# usb.net
KiCad netlist of a schematic drawn in Altium Designer
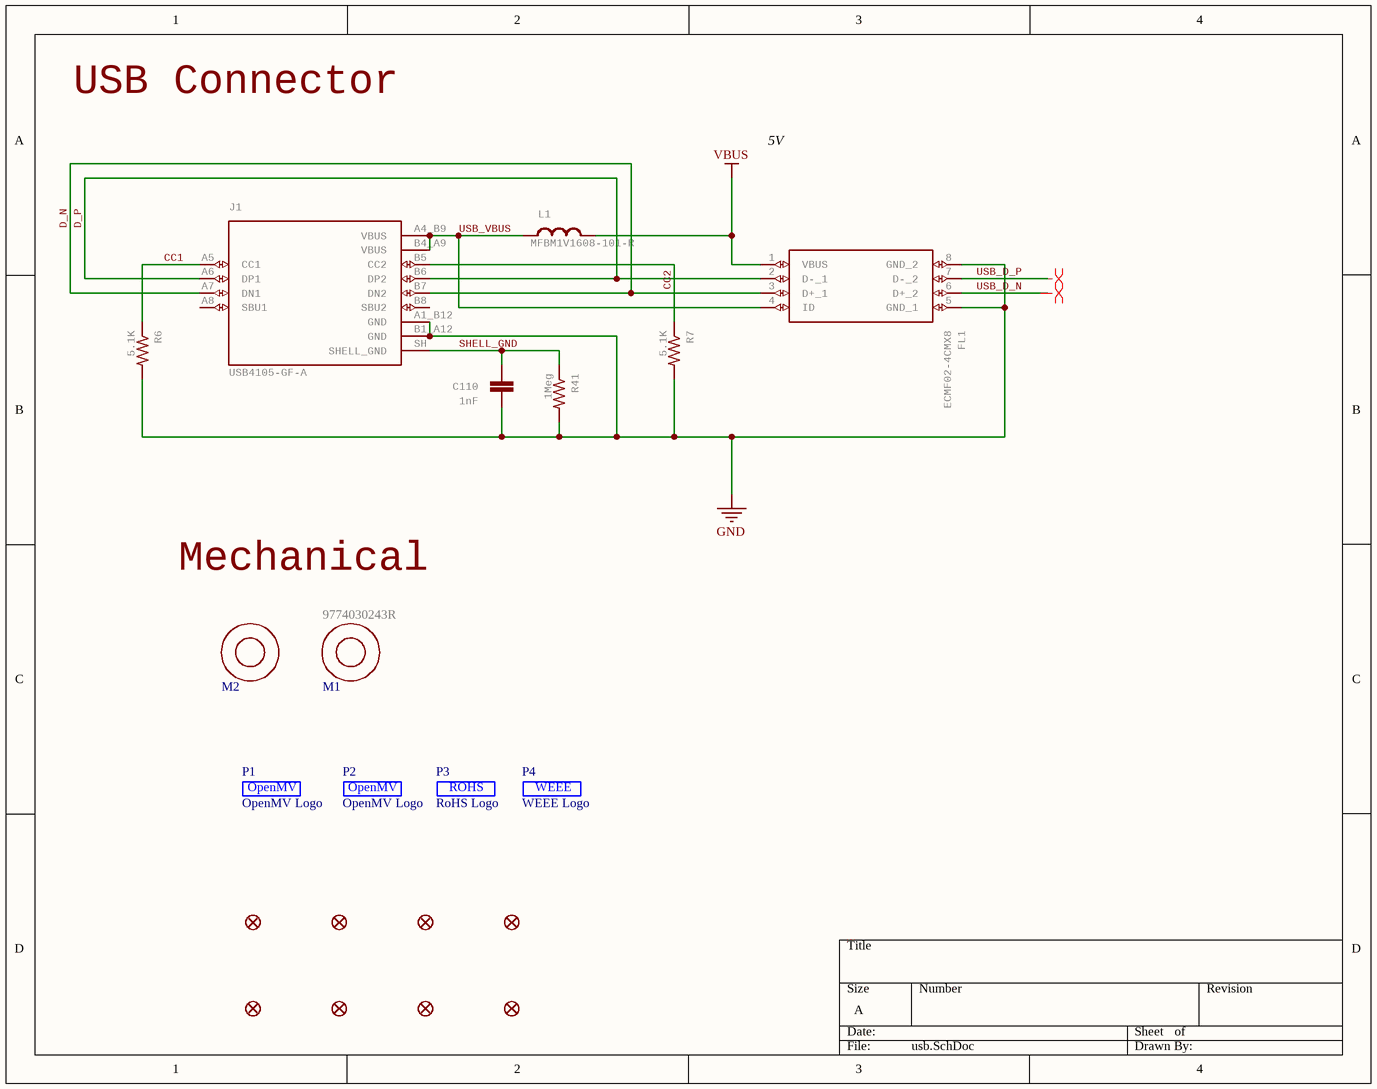
[diagram p0: usb.SchDoc]

(export (version "E")
  (design (tool "Eeschema 10.0.6"))
  (components
    (comp (ref "C110")
      (value "1nF")
      (footprint "0402-CAP")
      (description "Capacitor")
      (fields (field (name "MPN") "VJ0402Y102JXACW1BC"))
      (libsource (lib "rt10") (part "CAP0402-CAP"))
    )
    (comp (ref "FD1")
      (value "FIDUCIAL1X2")
      (footprint "FIDUCIAL-1X2")
      (fields (field (name "LIBRARYNAME") "SparkFun-Aesthetics"))
      (libsource (lib "rt10") (part "FIDUCIAL1X2"))
    )
    (comp (ref "FD2")
      (value "FIDUCIAL1X2")
      (footprint "FIDUCIAL-1X2")
      (fields (field (name "LIBRARYNAME") "SparkFun-Aesthetics"))
      (libsource (lib "rt10") (part "FIDUCIAL1X2"))
    )
    (comp (ref "FD3")
      (value "FIDUCIAL1X2")
      (footprint "FIDUCIAL-1X2")
      (fields (field (name "LIBRARYNAME") "SparkFun-Aesthetics"))
      (libsource (lib "rt10") (part "FIDUCIAL1X2"))
    )
    (comp (ref "FD4")
      (value "FIDUCIAL1X2")
      (footprint "FIDUCIAL-1X2")
      (fields (field (name "LIBRARYNAME") "SparkFun-Aesthetics"))
      (libsource (lib "rt10") (part "FIDUCIAL1X2"))
    )
    (comp (ref "FD5")
      (value "FIDUCIAL1X2")
      (footprint "FIDUCIAL-1X2")
      (fields (field (name "LIBRARYNAME") "SparkFun-Aesthetics"))
      (libsource (lib "rt10") (part "FIDUCIAL1X2"))
    )
    (comp (ref "FD6")
      (value "FIDUCIAL1X2")
      (footprint "FIDUCIAL-1X2")
      (fields (field (name "LIBRARYNAME") "SparkFun-Aesthetics"))
      (libsource (lib "rt10") (part "FIDUCIAL1X2"))
    )
    (comp (ref "FD7")
      (value "FIDUCIAL1X2")
      (footprint "FIDUCIAL-1X2")
      (fields (field (name "LIBRARYNAME") "SparkFun-Aesthetics"))
      (libsource (lib "rt10") (part "FIDUCIAL1X2"))
    )
    (comp (ref "FD8")
      (value "FIDUCIAL1X2")
      (footprint "FIDUCIAL-1X2")
      (fields (field (name "LIBRARYNAME") "SparkFun-Aesthetics"))
      (libsource (lib "rt10") (part "FIDUCIAL1X2"))
    )
    (comp (ref "FL1")
      (value "ECMF02-4CMX8")
      (footprint "ECMF024CMX8")
      (fields (field (name "MOUSER_PART_NUMBER") "511-ECMF02-4CMX8"))
      (libsource (lib "rt10") (part "ECMF02-4CMX8"))
    )
    (comp (ref "J1")
      (value "USB4105-GF-A")
      (footprint "GCT_USB4105-GF-A")
      (fields (field (name "MF") "GCT"))
      (libsource (lib "rt10") (part "USB4105-GF-A"))
    )
    (comp (ref "L1")
      (value "MFBM1V1608-101-R")
      (footprint "0603-RES")
      (libsource (lib "rt10") (part "INDUCTOR"))
    )
    (comp (ref "M1")
      (value "9774030243R")
      (footprint "9774030243R")
      (description "M2 3mm Standoff")
      (libsource (lib "rt10") (part "9774030243R"))
    )
    (comp (ref "M2")
      (value "9774030243R")
      (footprint "9774030243R")
      (description "M2 3mm Standoff")
      (libsource (lib "rt10") (part "9774030243R"))
    )
    (comp (ref "P1") (value "OpenMV Logo") (footprint "OMV-LOGO-SMALL") (libsource (lib "rt10") (part "OMV")))
    (comp (ref "P2") (value "OpenMV Logo") (footprint "OMV-LOGO-SMALL") (libsource (lib "rt10") (part "OMV")))
    (comp (ref "P3") (value "RoHS Logo") (footprint "ROHS") (libsource (lib "rt10") (part "ROHS")))
    (comp (ref "P4") (value "WEEE Logo") (footprint "WEEE") (libsource (lib "rt10") (part "WEEE")))
    (comp (ref "R6")
      (value "5.1K")
      (footprint "0402-RES")
      (description "ResistorBasic schematic elements and footprints for 0603, 1206, and PTH resistors.")
      (fields (field (name "MPN") "RC0402JR-075K1L"))
      (libsource (lib "rt10") (part "RESISTOR0402-RES"))
    )
    (comp (ref "R7")
      (value "5.1K")
      (footprint "0402-RES")
      (description "ResistorBasic schematic elements and footprints for 0603, 1206, and PTH resistors.")
      (fields (field (name "MPN") "RC0402JR-075K1L"))
      (libsource (lib "rt10") (part "RESISTOR0402-RES"))
    )
    (comp (ref "R41")
      (value "1Meg")
      (footprint "0402-RES")
      (description "Resistor")
      (fields (field (name "MPN") "CRCW04021M00FKEDC"))
      (libsource (lib "rt10") (part "RESISTOR0402-RES"))
    )
  )
  (nets
    (net (code "1") (name "/CC1") (class "Default")
      (node (ref "J1") (pin "A5") (pinfunction "CC1_A5") (pintype "bidirectional"))
      (node (ref "R6") (pin "1") (pinfunction "1_1") (pintype "passive"))
    )
    (net (code "2") (name "/CC2") (class "Default")
      (node (ref "J1") (pin "B5") (pinfunction "CC2_B5") (pintype "bidirectional"))
      (node (ref "R7") (pin "1") (pinfunction "1_1") (pintype "passive"))
    )
    (net (code "3") (name "/D_N") (class "Default")
      (node (ref "FL1") (pin "3") (pinfunction "D+_1_3") (pintype "bidirectional"))
      (node (ref "J1") (pin "A7") (pinfunction "DN1_A7") (pintype "bidirectional"))
      (node (ref "J1") (pin "B7") (pinfunction "DN2_B7") (pintype "bidirectional"))
    )
    (net (code "4") (name "/D_P") (class "Default")
      (node (ref "FL1") (pin "2") (pinfunction "D-_1_2") (pintype "bidirectional"))
      (node (ref "J1") (pin "A6") (pinfunction "DP1_A6") (pintype "bidirectional"))
      (node (ref "J1") (pin "B6") (pinfunction "DP2_B6") (pintype "bidirectional"))
    )
    (net (code "5") (name "/SHELL_GND") (class "Default")
      (node (ref "C110") (pin "1") (pinfunction "1_1") (pintype "passive"))
      (node (ref "J1") (pin "SH") (pinfunction "SHELL_GND_SH") (pintype "power_in"))
      (node (ref "R41") (pin "1") (pinfunction "1_1") (pintype "passive"))
    )
    (net (code "6") (name "/USB_D_N") (class "Default")
      (node (ref "FL1") (pin "6") (pinfunction "D+_2_6") (pintype "bidirectional"))
    )
    (net (code "7") (name "/USB_D_P") (class "Default")
      (node (ref "FL1") (pin "7") (pinfunction "D-_2_7") (pintype "bidirectional"))
    )
    (net (code "8") (name "/USB_VBUS") (class "Default")
      (node (ref "FL1") (pin "4") (pinfunction "ID_4") (pintype "bidirectional"))
      (node (ref "J1") (pin "A4_B9") (pinfunction "VBUS_A4_B9") (pintype "power_in"))
      (node (ref "J1") (pin "B4_A9") (pinfunction "VBUS_B4_A9") (pintype "power_in"))
      (node (ref "L1") (pin "1") (pinfunction "1_1") (pintype "passive"))
    )
    (net (code "9") (name "GND") (class "Default")
      (node (ref "C110") (pin "2") (pinfunction "2_2") (pintype "passive"))
      (node (ref "FL1") (pin "5") (pinfunction "GND_1_5") (pintype "bidirectional"))
      (node (ref "FL1") (pin "8") (pinfunction "GND_2_8") (pintype "bidirectional"))
      (node (ref "J1") (pin "A1_B12") (pinfunction "GND_A1_B12") (pintype "power_in"))
      (node (ref "J1") (pin "B1_A12") (pinfunction "GND_B1_A12") (pintype "power_in"))
      (node (ref "R41") (pin "2") (pinfunction "2_2") (pintype "passive"))
      (node (ref "R6") (pin "2") (pinfunction "2_2") (pintype "passive"))
      (node (ref "R7") (pin "2") (pinfunction "2_2") (pintype "passive"))
    )
    (net (code "10") (name "VBUS") (class "Default")
      (node (ref "FL1") (pin "1") (pinfunction "VBUS_1") (pintype "bidirectional"))
      (node (ref "L1") (pin "2") (pinfunction "2_2") (pintype "passive"))
    )
    (net (code "11") (name "unconnected-(J1-SBU1-PadA8)") (class "Default")
      (node (ref "J1") (pin "A8") (pinfunction "SBU1_A8") (pintype "bidirectional"))
    )
    (net (code "12") (name "unconnected-(J1-SBU2-PadB8)") (class "Default")
      (node (ref "J1") (pin "B8") (pinfunction "SBU2_B8") (pintype "bidirectional"))
    )
  )
)
